# Adafruit_PCA9685.net
KiCad netlist of a schematic drawn in EAGLE
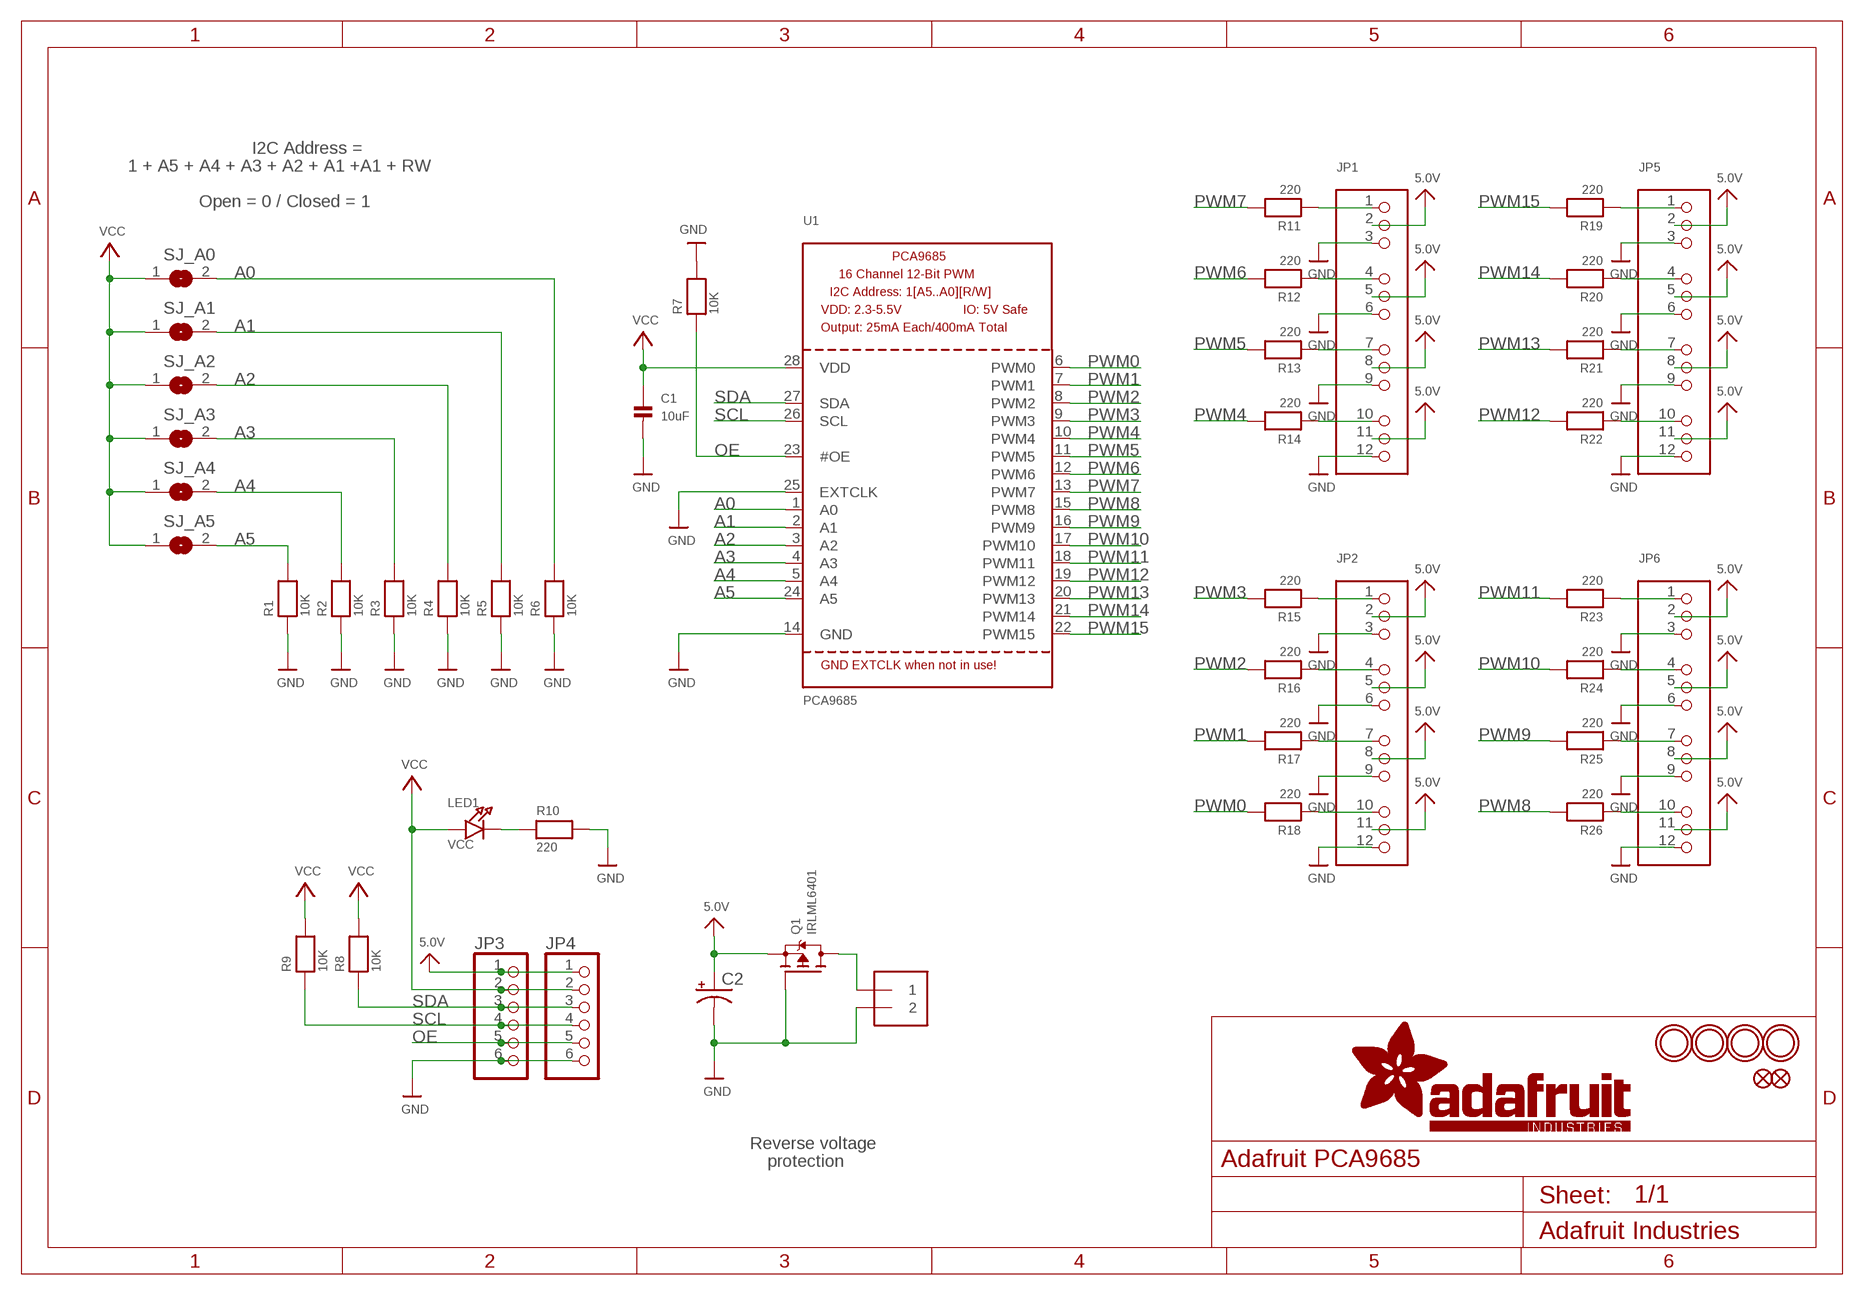
[diagram p0: schematic, sheet 1]

(export (version "E")
  (design (tool "Eeschema 10.0.6"))
  (components
    (comp (ref "C1")
      (value "10uF")
      (footprint "eagle-import:0805")
      (libsource (lib "eagle-import") (part "CAP_CERAMIC0805"))
    )
    (comp (ref "C2")
      (value "CPOL-USE3.5-8")
      (footprint "eagle-import:E3,5-8")
      (libsource (lib "eagle-import") (part "CPOL-USE3.5-8"))
    )
    (comp (ref "FID1")
      (value "FIDUCIAL\"\"")
      (footprint "eagle-import:FIDUCIAL_1MM")
      (libsource (lib "eagle-import") (part "FIDUCIAL{dblquote}{dblquote}"))
    )
    (comp (ref "FID2")
      (value "FIDUCIAL\"\"")
      (footprint "eagle-import:FIDUCIAL_1MM")
      (libsource (lib "eagle-import") (part "FIDUCIAL{dblquote}{dblquote}"))
    )
    (comp (ref "J1")
      (value "TERMBLOCK_1X2-3.5MM")
      (footprint "eagle-import:1X2-3.5MM")
      (libsource (lib "eagle-import") (part "TERMBLOCK_1X2-3.5MM"))
    )
    (comp (ref "JP1")
      (value "HEADER-3X04")
      (footprint "eagle-import:3X04")
      (libsource (lib "eagle-import") (part "HEADER-3X04"))
    )
    (comp (ref "JP2")
      (value "HEADER-3X04")
      (footprint "eagle-import:3X04")
      (libsource (lib "eagle-import") (part "HEADER-3X04"))
    )
    (comp (ref "JP3")
      (value "PINHD-1X6CB")
      (footprint "eagle-import:1X06-CLEANBIG")
      (libsource (lib "eagle-import") (part "PINHD-1X6CB"))
    )
    (comp (ref "JP4")
      (value "PINHD-1X6CB")
      (footprint "eagle-import:1X06-CLEANBIG")
      (libsource (lib "eagle-import") (part "PINHD-1X6CB"))
    )
    (comp (ref "JP5")
      (value "HEADER-3X04")
      (footprint "eagle-import:3X04")
      (libsource (lib "eagle-import") (part "HEADER-3X04"))
    )
    (comp (ref "JP6")
      (value "HEADER-3X04")
      (footprint "eagle-import:3X04")
      (libsource (lib "eagle-import") (part "HEADER-3X04"))
    )
    (comp (ref "LED1")
      (value "VCC")
      (footprint "eagle-import:CHIPLED_0805")
      (libsource (lib "eagle-import") (part "LED0805"))
    )
    (comp (ref "Q1")
      (value "IRLML6401")
      (footprint "eagle-import:SOT23-WIDE")
      (libsource (lib "eagle-import") (part "MOSFET-PWIDE"))
    )
    (comp (ref "R1")
      (value "10K")
      (footprint "eagle-import:0805")
      (libsource (lib "eagle-import") (part "RESISTOR0805"))
    )
    (comp (ref "R2")
      (value "10K")
      (footprint "eagle-import:0805")
      (libsource (lib "eagle-import") (part "RESISTOR0805"))
    )
    (comp (ref "R3")
      (value "10K")
      (footprint "eagle-import:0805")
      (libsource (lib "eagle-import") (part "RESISTOR0805"))
    )
    (comp (ref "R4")
      (value "10K")
      (footprint "eagle-import:0805")
      (libsource (lib "eagle-import") (part "RESISTOR0805"))
    )
    (comp (ref "R5")
      (value "10K")
      (footprint "eagle-import:0805")
      (libsource (lib "eagle-import") (part "RESISTOR0805"))
    )
    (comp (ref "R6")
      (value "10K")
      (footprint "eagle-import:0805")
      (libsource (lib "eagle-import") (part "RESISTOR0805"))
    )
    (comp (ref "R7")
      (value "10K")
      (footprint "eagle-import:0805")
      (libsource (lib "eagle-import") (part "RESISTOR0805"))
    )
    (comp (ref "R8")
      (value "10K")
      (footprint "eagle-import:0805")
      (libsource (lib "eagle-import") (part "RESISTOR0805"))
    )
    (comp (ref "R9")
      (value "10K")
      (footprint "eagle-import:0805")
      (libsource (lib "eagle-import") (part "RESISTOR0805"))
    )
    (comp (ref "R10")
      (value "220")
      (footprint "eagle-import:0805")
      (libsource (lib "eagle-import") (part "RESISTOR0805"))
    )
    (comp (ref "R11")
      (value "220")
      (footprint "eagle-import:0805")
      (libsource (lib "eagle-import") (part "RESISTOR0805"))
    )
    (comp (ref "R12")
      (value "220")
      (footprint "eagle-import:0805")
      (libsource (lib "eagle-import") (part "RESISTOR0805"))
    )
    (comp (ref "R13")
      (value "220")
      (footprint "eagle-import:0805")
      (libsource (lib "eagle-import") (part "RESISTOR0805"))
    )
    (comp (ref "R14")
      (value "220")
      (footprint "eagle-import:0805")
      (libsource (lib "eagle-import") (part "RESISTOR0805"))
    )
    (comp (ref "R15")
      (value "220")
      (footprint "eagle-import:0805")
      (libsource (lib "eagle-import") (part "RESISTOR0805"))
    )
    (comp (ref "R16")
      (value "220")
      (footprint "eagle-import:0805")
      (libsource (lib "eagle-import") (part "RESISTOR0805"))
    )
    (comp (ref "R17")
      (value "220")
      (footprint "eagle-import:0805")
      (libsource (lib "eagle-import") (part "RESISTOR0805"))
    )
    (comp (ref "R18")
      (value "220")
      (footprint "eagle-import:0805")
      (libsource (lib "eagle-import") (part "RESISTOR0805"))
    )
    (comp (ref "R19")
      (value "220")
      (footprint "eagle-import:0805")
      (libsource (lib "eagle-import") (part "RESISTOR0805"))
    )
    (comp (ref "R20")
      (value "220")
      (footprint "eagle-import:0805")
      (libsource (lib "eagle-import") (part "RESISTOR0805"))
    )
    (comp (ref "R21")
      (value "220")
      (footprint "eagle-import:0805")
      (libsource (lib "eagle-import") (part "RESISTOR0805"))
    )
    (comp (ref "R22")
      (value "220")
      (footprint "eagle-import:0805")
      (libsource (lib "eagle-import") (part "RESISTOR0805"))
    )
    (comp (ref "R23")
      (value "220")
      (footprint "eagle-import:0805")
      (libsource (lib "eagle-import") (part "RESISTOR0805"))
    )
    (comp (ref "R24")
      (value "220")
      (footprint "eagle-import:0805")
      (libsource (lib "eagle-import") (part "RESISTOR0805"))
    )
    (comp (ref "R25")
      (value "220")
      (footprint "eagle-import:0805")
      (libsource (lib "eagle-import") (part "RESISTOR0805"))
    )
    (comp (ref "R26")
      (value "220")
      (footprint "eagle-import:0805")
      (libsource (lib "eagle-import") (part "RESISTOR0805"))
    )
    (comp (ref "SJ_A0")
      (value "SOLDERJUMPERREFLOW_NOPASTE")
      (footprint "eagle-import:SOLDERJUMPER_REFLOW_NOPASTE")
      (libsource (lib "eagle-import") (part "SOLDERJUMPERREFLOW_NOPASTE"))
    )
    (comp (ref "SJ_A1")
      (value "SOLDERJUMPERREFLOW_NOPASTE")
      (footprint "eagle-import:SOLDERJUMPER_REFLOW_NOPASTE")
      (libsource (lib "eagle-import") (part "SOLDERJUMPERREFLOW_NOPASTE"))
    )
    (comp (ref "SJ_A2")
      (value "SOLDERJUMPERREFLOW_NOPASTE")
      (footprint "eagle-import:SOLDERJUMPER_REFLOW_NOPASTE")
      (libsource (lib "eagle-import") (part "SOLDERJUMPERREFLOW_NOPASTE"))
    )
    (comp (ref "SJ_A3")
      (value "SOLDERJUMPERREFLOW_NOPASTE")
      (footprint "eagle-import:SOLDERJUMPER_REFLOW_NOPASTE")
      (libsource (lib "eagle-import") (part "SOLDERJUMPERREFLOW_NOPASTE"))
    )
    (comp (ref "SJ_A4")
      (value "SOLDERJUMPERREFLOW_NOPASTE")
      (footprint "eagle-import:SOLDERJUMPER_REFLOW_NOPASTE")
      (libsource (lib "eagle-import") (part "SOLDERJUMPERREFLOW_NOPASTE"))
    )
    (comp (ref "SJ_A5")
      (value "SOLDERJUMPERREFLOW_NOPASTE")
      (footprint "eagle-import:SOLDERJUMPER_REFLOW_NOPASTE")
      (libsource (lib "eagle-import") (part "SOLDERJUMPERREFLOW_NOPASTE"))
    )
    (comp (ref "U$47")
      (value "MOUNTINGHOLE2.5")
      (footprint "eagle-import:MOUNTINGHOLE_2.5_PLATED")
      (libsource (lib "eagle-import") (part "MOUNTINGHOLE2.5"))
    )
    (comp (ref "U$48")
      (value "MOUNTINGHOLE2.5")
      (footprint "eagle-import:MOUNTINGHOLE_2.5_PLATED")
      (libsource (lib "eagle-import") (part "MOUNTINGHOLE2.5"))
    )
    (comp (ref "U$49")
      (value "MOUNTINGHOLE2.5")
      (footprint "eagle-import:MOUNTINGHOLE_2.5_PLATED")
      (libsource (lib "eagle-import") (part "MOUNTINGHOLE2.5"))
    )
    (comp (ref "U$50")
      (value "MOUNTINGHOLE2.5")
      (footprint "eagle-import:MOUNTINGHOLE_2.5_PLATED")
      (libsource (lib "eagle-import") (part "MOUNTINGHOLE2.5"))
    )
    (comp (ref "U1")
      (value "PCA9685")
      (footprint "eagle-import:TSSOP28")
      (libsource (lib "eagle-import") (part "PCA9685"))
    )
  )
  (nets
    (net (code "1") (name "/A0") (class "Default")
      (node (ref "R6") (pin "2") (pinfunction "2_2") (pintype "passive"))
      (node (ref "SJ_A0") (pin "2") (pinfunction "2_2") (pintype "passive"))
      (node (ref "U1") (pin "1") (pinfunction "A0_1") (pintype "bidirectional"))
    )
    (net (code "2") (name "/A1") (class "Default")
      (node (ref "R5") (pin "2") (pinfunction "2_2") (pintype "passive"))
      (node (ref "SJ_A1") (pin "2") (pinfunction "2_2") (pintype "passive"))
      (node (ref "U1") (pin "2") (pinfunction "A1_2") (pintype "bidirectional"))
    )
    (net (code "3") (name "/A2") (class "Default")
      (node (ref "R4") (pin "2") (pinfunction "2_2") (pintype "passive"))
      (node (ref "SJ_A2") (pin "2") (pinfunction "2_2") (pintype "passive"))
      (node (ref "U1") (pin "3") (pinfunction "A2_3") (pintype "bidirectional"))
    )
    (net (code "4") (name "/A3") (class "Default")
      (node (ref "R3") (pin "2") (pinfunction "2_2") (pintype "passive"))
      (node (ref "SJ_A3") (pin "2") (pinfunction "2_2") (pintype "passive"))
      (node (ref "U1") (pin "4") (pinfunction "A3_4") (pintype "bidirectional"))
    )
    (net (code "5") (name "/A4") (class "Default")
      (node (ref "R2") (pin "2") (pinfunction "2_2") (pintype "passive"))
      (node (ref "SJ_A4") (pin "2") (pinfunction "2_2") (pintype "passive"))
      (node (ref "U1") (pin "5") (pinfunction "A4_5") (pintype "bidirectional"))
    )
    (net (code "6") (name "/A5") (class "Default")
      (node (ref "R1") (pin "2") (pinfunction "2_2") (pintype "passive"))
      (node (ref "SJ_A5") (pin "2") (pinfunction "2_2") (pintype "passive"))
      (node (ref "U1") (pin "24") (pinfunction "A5_24") (pintype "bidirectional"))
    )
    (net (code "7") (name "/OE") (class "Default")
      (node (ref "JP3") (pin "5") (pinfunction "5_5") (pintype "passive"))
      (node (ref "JP4") (pin "5") (pinfunction "5_5") (pintype "passive"))
      (node (ref "R7") (pin "1") (pinfunction "1_1") (pintype "passive"))
      (node (ref "U1") (pin "23") (pinfunction "#OE_23") (pintype "input"))
    )
    (net (code "8") (name "/PWM0") (class "Default")
      (node (ref "R18") (pin "2") (pinfunction "2_2") (pintype "passive"))
      (node (ref "U1") (pin "6") (pinfunction "PWM0_6") (pintype "output"))
    )
    (net (code "9") (name "/PWM1") (class "Default")
      (node (ref "R17") (pin "2") (pinfunction "2_2") (pintype "passive"))
      (node (ref "U1") (pin "7") (pinfunction "PWM1_7") (pintype "output"))
    )
    (net (code "10") (name "/PWM2") (class "Default")
      (node (ref "R16") (pin "2") (pinfunction "2_2") (pintype "passive"))
      (node (ref "U1") (pin "8") (pinfunction "PWM2_8") (pintype "output"))
    )
    (net (code "11") (name "/PWM3") (class "Default")
      (node (ref "R15") (pin "2") (pinfunction "2_2") (pintype "passive"))
      (node (ref "U1") (pin "9") (pinfunction "PWM3_9") (pintype "output"))
    )
    (net (code "12") (name "/PWM4") (class "Default")
      (node (ref "R14") (pin "2") (pinfunction "2_2") (pintype "passive"))
      (node (ref "U1") (pin "10") (pinfunction "PWM4_10") (pintype "output"))
    )
    (net (code "13") (name "/PWM5") (class "Default")
      (node (ref "R13") (pin "2") (pinfunction "2_2") (pintype "passive"))
      (node (ref "U1") (pin "11") (pinfunction "PWM5_11") (pintype "output"))
    )
    (net (code "14") (name "/PWM6") (class "Default")
      (node (ref "R12") (pin "2") (pinfunction "2_2") (pintype "passive"))
      (node (ref "U1") (pin "12") (pinfunction "PWM6_12") (pintype "output"))
    )
    (net (code "15") (name "/PWM7") (class "Default")
      (node (ref "R11") (pin "2") (pinfunction "2_2") (pintype "passive"))
      (node (ref "U1") (pin "13") (pinfunction "PWM7_13") (pintype "output"))
    )
    (net (code "16") (name "/PWM8") (class "Default")
      (node (ref "R26") (pin "2") (pinfunction "2_2") (pintype "passive"))
      (node (ref "U1") (pin "15") (pinfunction "PWM8_15") (pintype "output"))
    )
    (net (code "17") (name "/PWM9") (class "Default")
      (node (ref "R25") (pin "2") (pinfunction "2_2") (pintype "passive"))
      (node (ref "U1") (pin "16") (pinfunction "PWM9_16") (pintype "output"))
    )
    (net (code "18") (name "/PWM10") (class "Default")
      (node (ref "R24") (pin "2") (pinfunction "2_2") (pintype "passive"))
      (node (ref "U1") (pin "17") (pinfunction "PWM10_17") (pintype "output"))
    )
    (net (code "19") (name "/PWM11") (class "Default")
      (node (ref "R23") (pin "2") (pinfunction "2_2") (pintype "passive"))
      (node (ref "U1") (pin "18") (pinfunction "PWM11_18") (pintype "output"))
    )
    (net (code "20") (name "/PWM12") (class "Default")
      (node (ref "R22") (pin "2") (pinfunction "2_2") (pintype "passive"))
      (node (ref "U1") (pin "19") (pinfunction "PWM12_19") (pintype "output"))
    )
    (net (code "21") (name "/PWM13") (class "Default")
      (node (ref "R21") (pin "2") (pinfunction "2_2") (pintype "passive"))
      (node (ref "U1") (pin "20") (pinfunction "PWM13_20") (pintype "output"))
    )
    (net (code "22") (name "/PWM14") (class "Default")
      (node (ref "R20") (pin "2") (pinfunction "2_2") (pintype "passive"))
      (node (ref "U1") (pin "21") (pinfunction "PWM14_21") (pintype "output"))
    )
    (net (code "23") (name "/PWM15") (class "Default")
      (node (ref "R19") (pin "2") (pinfunction "2_2") (pintype "passive"))
      (node (ref "U1") (pin "22") (pinfunction "PWM15_22") (pintype "output"))
    )
    (net (code "24") (name "/SCL") (class "Default")
      (node (ref "JP3") (pin "4") (pinfunction "4_4") (pintype "passive"))
      (node (ref "JP4") (pin "4") (pinfunction "4_4") (pintype "passive"))
      (node (ref "R9") (pin "1") (pinfunction "1_1") (pintype "passive"))
      (node (ref "U1") (pin "26") (pinfunction "SCL_26") (pintype "bidirectional"))
    )
    (net (code "25") (name "/SDA") (class "Default")
      (node (ref "JP3") (pin "3") (pinfunction "3_3") (pintype "passive"))
      (node (ref "JP4") (pin "3") (pinfunction "3_3") (pintype "passive"))
      (node (ref "R8") (pin "1") (pinfunction "1_1") (pintype "passive"))
      (node (ref "U1") (pin "27") (pinfunction "SDA_27") (pintype "bidirectional"))
    )
    (net (code "26") (name "5.0V") (class "Default")
      (node (ref "C2") (pin "+") (pinfunction "+_+") (pintype "passive"))
      (node (ref "JP1") (pin "11") (pinfunction "11_11") (pintype "passive"))
      (node (ref "JP1") (pin "2") (pinfunction "2_2") (pintype "passive"))
      (node (ref "JP1") (pin "5") (pinfunction "5_5") (pintype "passive"))
      (node (ref "JP1") (pin "8") (pinfunction "8_8") (pintype "passive"))
      (node (ref "JP2") (pin "11") (pinfunction "11_11") (pintype "passive"))
      (node (ref "JP2") (pin "2") (pinfunction "2_2") (pintype "passive"))
      (node (ref "JP2") (pin "5") (pinfunction "5_5") (pintype "passive"))
      (node (ref "JP2") (pin "8") (pinfunction "8_8") (pintype "passive"))
      (node (ref "JP3") (pin "1") (pinfunction "1_1") (pintype "passive"))
      (node (ref "JP4") (pin "1") (pinfunction "1_1") (pintype "passive"))
      (node (ref "JP5") (pin "11") (pinfunction "11_11") (pintype "passive"))
      (node (ref "JP5") (pin "2") (pinfunction "2_2") (pintype "passive"))
      (node (ref "JP5") (pin "5") (pinfunction "5_5") (pintype "passive"))
      (node (ref "JP5") (pin "8") (pinfunction "8_8") (pintype "passive"))
      (node (ref "JP6") (pin "11") (pinfunction "11_11") (pintype "passive"))
      (node (ref "JP6") (pin "2") (pinfunction "2_2") (pintype "passive"))
      (node (ref "JP6") (pin "5") (pinfunction "5_5") (pintype "passive"))
      (node (ref "JP6") (pin "8") (pinfunction "8_8") (pintype "passive"))
      (node (ref "Q1") (pin "2") (pinfunction "S_2") (pintype "passive"))
    )
    (net (code "27") (name "GND") (class "Default")
      (node (ref "C1") (pin "2") (pinfunction "P$2_2") (pintype "passive"))
      (node (ref "C2") (pin "-") (pinfunction "-_-") (pintype "passive"))
      (node (ref "J1") (pin "2") (pinfunction "2_2") (pintype "passive"))
      (node (ref "JP1") (pin "12") (pinfunction "12_12") (pintype "passive"))
      (node (ref "JP1") (pin "3") (pinfunction "3_3") (pintype "passive"))
      (node (ref "JP1") (pin "6") (pinfunction "6_6") (pintype "passive"))
      (node (ref "JP1") (pin "9") (pinfunction "9_9") (pintype "passive"))
      (node (ref "JP2") (pin "12") (pinfunction "12_12") (pintype "passive"))
      (node (ref "JP2") (pin "3") (pinfunction "3_3") (pintype "passive"))
      (node (ref "JP2") (pin "6") (pinfunction "6_6") (pintype "passive"))
      (node (ref "JP2") (pin "9") (pinfunction "9_9") (pintype "passive"))
      (node (ref "JP3") (pin "6") (pinfunction "6_6") (pintype "passive"))
      (node (ref "JP4") (pin "6") (pinfunction "6_6") (pintype "passive"))
      (node (ref "JP5") (pin "12") (pinfunction "12_12") (pintype "passive"))
      (node (ref "JP5") (pin "3") (pinfunction "3_3") (pintype "passive"))
      (node (ref "JP5") (pin "6") (pinfunction "6_6") (pintype "passive"))
      (node (ref "JP5") (pin "9") (pinfunction "9_9") (pintype "passive"))
      (node (ref "JP6") (pin "12") (pinfunction "12_12") (pintype "passive"))
      (node (ref "JP6") (pin "3") (pinfunction "3_3") (pintype "passive"))
      (node (ref "JP6") (pin "6") (pinfunction "6_6") (pintype "passive"))
      (node (ref "JP6") (pin "9") (pinfunction "9_9") (pintype "passive"))
      (node (ref "Q1") (pin "1") (pinfunction "G_1") (pintype "passive"))
      (node (ref "R1") (pin "1") (pinfunction "1_1") (pintype "passive"))
      (node (ref "R10") (pin "2") (pinfunction "2_2") (pintype "passive"))
      (node (ref "R2") (pin "1") (pinfunction "1_1") (pintype "passive"))
      (node (ref "R3") (pin "1") (pinfunction "1_1") (pintype "passive"))
      (node (ref "R4") (pin "1") (pinfunction "1_1") (pintype "passive"))
      (node (ref "R5") (pin "1") (pinfunction "1_1") (pintype "passive"))
      (node (ref "R6") (pin "1") (pinfunction "1_1") (pintype "passive"))
      (node (ref "R7") (pin "2") (pinfunction "2_2") (pintype "passive"))
      (node (ref "U1") (pin "14") (pinfunction "GND_14") (pintype "power_in"))
      (node (ref "U1") (pin "25") (pinfunction "EXTCLK_25") (pintype "input"))
    )
    (net (code "28") (name "Net-(JP1-Pad1)") (class "Default")
      (node (ref "JP1") (pin "1") (pinfunction "1_1") (pintype "passive"))
      (node (ref "R11") (pin "1") (pinfunction "1_1") (pintype "passive"))
    )
    (net (code "29") (name "Net-(JP1-Pad4)") (class "Default")
      (node (ref "JP1") (pin "4") (pinfunction "4_4") (pintype "passive"))
      (node (ref "R12") (pin "1") (pinfunction "1_1") (pintype "passive"))
    )
    (net (code "30") (name "Net-(JP1-Pad7)") (class "Default")
      (node (ref "JP1") (pin "7") (pinfunction "7_7") (pintype "passive"))
      (node (ref "R13") (pin "1") (pinfunction "1_1") (pintype "passive"))
    )
    (net (code "31") (name "Net-(JP1-Pad10)") (class "Default")
      (node (ref "JP1") (pin "10") (pinfunction "10_10") (pintype "passive"))
      (node (ref "R14") (pin "1") (pinfunction "1_1") (pintype "passive"))
    )
    (net (code "32") (name "Net-(JP2-Pad1)") (class "Default")
      (node (ref "JP2") (pin "1") (pinfunction "1_1") (pintype "passive"))
      (node (ref "R15") (pin "1") (pinfunction "1_1") (pintype "passive"))
    )
    (net (code "33") (name "Net-(JP2-Pad4)") (class "Default")
      (node (ref "JP2") (pin "4") (pinfunction "4_4") (pintype "passive"))
      (node (ref "R16") (pin "1") (pinfunction "1_1") (pintype "passive"))
    )
    (net (code "34") (name "Net-(JP2-Pad7)") (class "Default")
      (node (ref "JP2") (pin "7") (pinfunction "7_7") (pintype "passive"))
      (node (ref "R17") (pin "1") (pinfunction "1_1") (pintype "passive"))
    )
    (net (code "35") (name "Net-(JP2-Pad10)") (class "Default")
      (node (ref "JP2") (pin "10") (pinfunction "10_10") (pintype "passive"))
      (node (ref "R18") (pin "1") (pinfunction "1_1") (pintype "passive"))
    )
    (net (code "36") (name "Net-(JP5-Pad1)") (class "Default")
      (node (ref "JP5") (pin "1") (pinfunction "1_1") (pintype "passive"))
      (node (ref "R19") (pin "1") (pinfunction "1_1") (pintype "passive"))
    )
    (net (code "37") (name "Net-(JP5-Pad4)") (class "Default")
      (node (ref "JP5") (pin "4") (pinfunction "4_4") (pintype "passive"))
      (node (ref "R20") (pin "1") (pinfunction "1_1") (pintype "passive"))
    )
    (net (code "38") (name "Net-(JP5-Pad7)") (class "Default")
      (node (ref "JP5") (pin "7") (pinfunction "7_7") (pintype "passive"))
      (node (ref "R21") (pin "1") (pinfunction "1_1") (pintype "passive"))
    )
    (net (code "39") (name "Net-(JP5-Pad10)") (class "Default")
      (node (ref "JP5") (pin "10") (pinfunction "10_10") (pintype "passive"))
      (node (ref "R22") (pin "1") (pinfunction "1_1") (pintype "passive"))
    )
    (net (code "40") (name "Net-(JP6-Pad1)") (class "Default")
      (node (ref "JP6") (pin "1") (pinfunction "1_1") (pintype "passive"))
      (node (ref "R23") (pin "1") (pinfunction "1_1") (pintype "passive"))
    )
    (net (code "41") (name "Net-(JP6-Pad4)") (class "Default")
      (node (ref "JP6") (pin "4") (pinfunction "4_4") (pintype "passive"))
      (node (ref "R24") (pin "1") (pinfunction "1_1") (pintype "passive"))
    )
    (net (code "42") (name "Net-(JP6-Pad7)") (class "Default")
      (node (ref "JP6") (pin "7") (pinfunction "7_7") (pintype "passive"))
      (node (ref "R25") (pin "1") (pinfunction "1_1") (pintype "passive"))
    )
    (net (code "43") (name "Net-(JP6-Pad10)") (class "Default")
      (node (ref "JP6") (pin "10") (pinfunction "10_10") (pintype "passive"))
      (node (ref "R26") (pin "1") (pinfunction "1_1") (pintype "passive"))
    )
    (net (code "44") (name "Net-(LED1-PadC)") (class "Default")
      (node (ref "LED1") (pin "C") (pinfunction "C_C") (pintype "passive"))
      (node (ref "R10") (pin "1") (pinfunction "1_1") (pintype "passive"))
    )
    (net (code "45") (name "Net-(Q1-D)") (class "Default")
      (node (ref "J1") (pin "1") (pinfunction "1_1") (pintype "passive"))
      (node (ref "Q1") (pin "3") (pinfunction "D_3") (pintype "passive"))
    )
    (net (code "46") (name "VCC") (class "Default")
      (node (ref "C1") (pin "1") (pinfunction "P$1_1") (pintype "passive"))
      (node (ref "JP3") (pin "2") (pinfunction "2_2") (pintype "passive"))
      (node (ref "JP4") (pin "2") (pinfunction "2_2") (pintype "passive"))
      (node (ref "LED1") (pin "A") (pinfunction "A_A") (pintype "passive"))
      (node (ref "R8") (pin "2") (pinfunction "2_2") (pintype "passive"))
      (node (ref "R9") (pin "2") (pinfunction "2_2") (pintype "passive"))
      (node (ref "SJ_A0") (pin "1") (pinfunction "1_1") (pintype "passive"))
      (node (ref "SJ_A1") (pin "1") (pinfunction "1_1") (pintype "passive"))
      (node (ref "SJ_A2") (pin "1") (pinfunction "1_1") (pintype "passive"))
      (node (ref "SJ_A3") (pin "1") (pinfunction "1_1") (pintype "passive"))
      (node (ref "SJ_A4") (pin "1") (pinfunction "1_1") (pintype "passive"))
      (node (ref "SJ_A5") (pin "1") (pinfunction "1_1") (pintype "passive"))
      (node (ref "U1") (pin "28") (pinfunction "VDD_28") (pintype "power_in"))
    )
  )
)
